# main.net
KiCad netlist of a schematic drawn in EAGLE
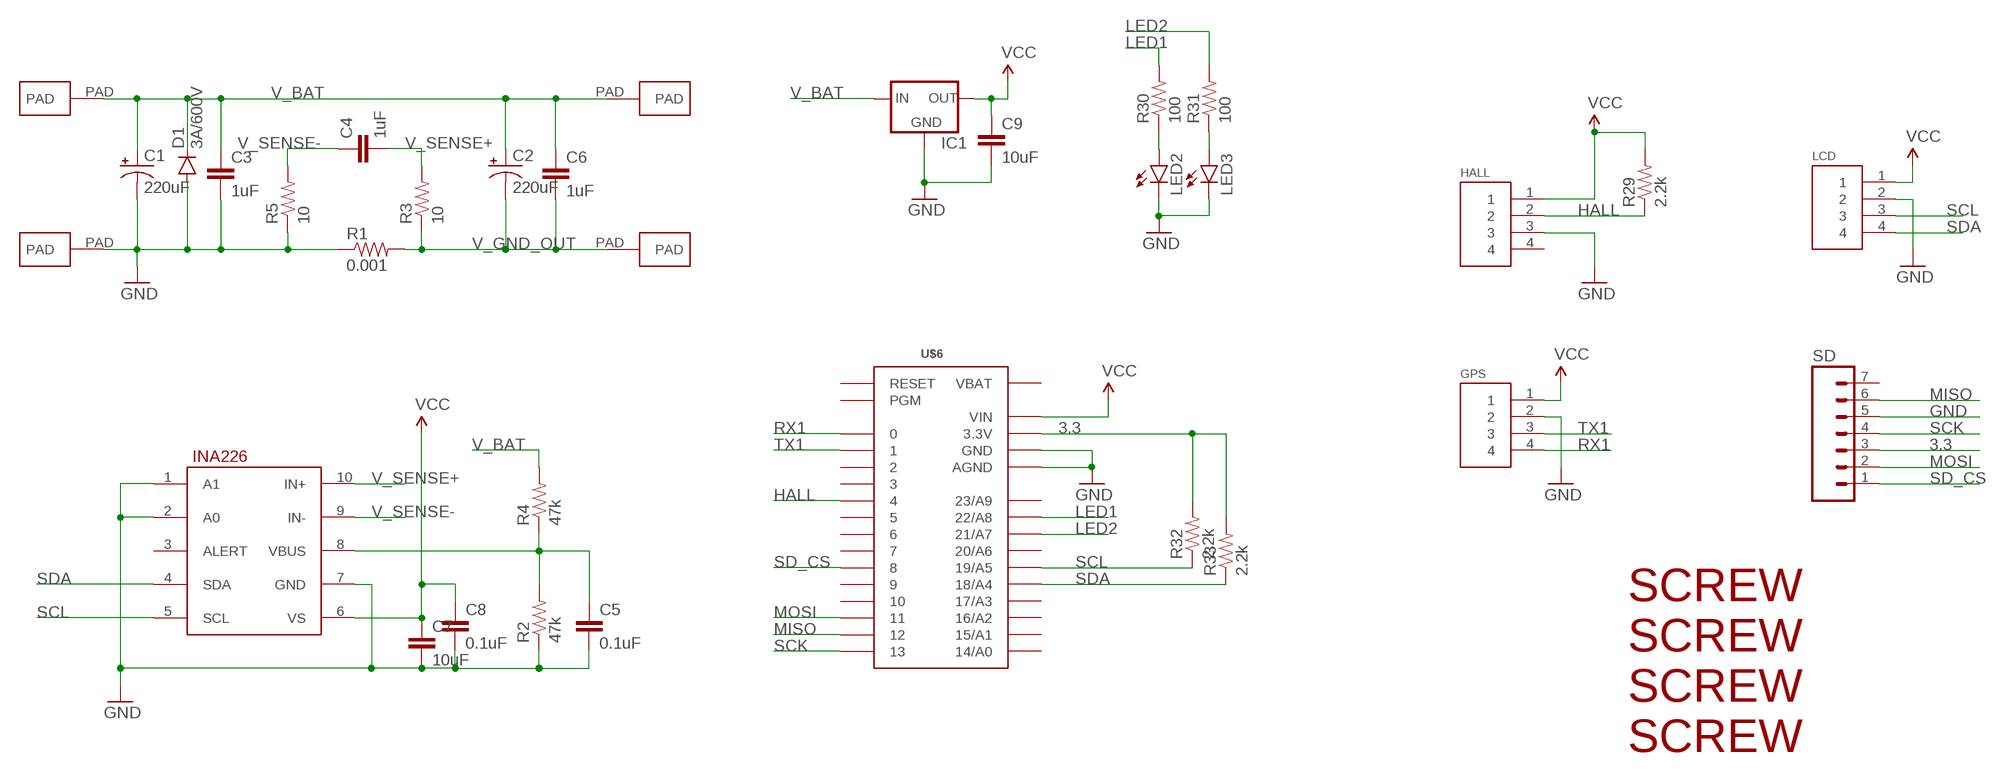
[diagram p0: schematic, sheet 1]

(export (version "E")
  (design (tool "Eeschema 10.0.6"))
  (components
    (comp (ref "C1")
      (value "220uF")
      (footprint "eagle-import:CPOL-RADIAL-1000UF-25V")
      (libsource (lib "eagle-import") (part "CAP_POLPTH4"))
    )
    (comp (ref "C2")
      (value "220uF")
      (footprint "eagle-import:CPOL-RADIAL-1000UF-25V")
      (libsource (lib "eagle-import") (part "CAP_POLPTH4"))
    )
    (comp (ref "C3")
      (value "1uF")
      (footprint "eagle-import:1206")
      (libsource (lib "eagle-import") (part "CAP1206"))
    )
    (comp (ref "C4")
      (value "1uF")
      (footprint "eagle-import:1206")
      (libsource (lib "eagle-import") (part "CAP1206"))
    )
    (comp (ref "C5")
      (value "0.1uF")
      (footprint "eagle-import:0603-CAP")
      (libsource (lib "eagle-import") (part "SparkFun-Passives_CAP0603-CAP"))
    )
    (comp (ref "C6")
      (value "1uF")
      (footprint "eagle-import:1206")
      (libsource (lib "eagle-import") (part "CAP1206"))
    )
    (comp (ref "C7")
      (value "10uF")
      (footprint "eagle-import:0805")
      (libsource (lib "eagle-import") (part "SparkFun-Passives_CAP0805"))
    )
    (comp (ref "C8")
      (value "0.1uF")
      (footprint "eagle-import:0603-CAP")
      (libsource (lib "eagle-import") (part "SparkFun-Passives_CAP0603-CAP"))
    )
    (comp (ref "C9")
      (value "10uF")
      (footprint "eagle-import:0805")
      (libsource (lib "eagle-import") (part "SparkFun-Passives_CAP0805"))
    )
    (comp (ref "D1")
      (value "3A/600V")
      (footprint "eagle-import:SMC")
      (libsource (lib "eagle-import") (part "DIODEES3J"))
    )
    (comp (ref "GPS")
      (value "GPS")
      (footprint "eagle-import:4PINVALULOK")
      (libsource (lib "eagle-import") (part "HEADER4VALULOK"))
    )
    (comp (ref "HALL")
      (value "HEADER4VALULOK")
      (footprint "eagle-import:4PINVALULOK")
      (libsource (lib "eagle-import") (part "HEADER4VALULOK"))
    )
    (comp (ref "IC1")
      (value "V_REG_78XXSINK")
      (footprint "eagle-import:TO220-IGO")
      (libsource (lib "eagle-import") (part "V_REG_78XXSINK"))
    )
    (comp (ref "LCD")
      (value "GPS")
      (footprint "eagle-import:4PINVALULOK")
      (libsource (lib "eagle-import") (part "HEADER4VALULOK"))
    )
    (comp (ref "LED2")
      (value "LED1206")
      (footprint "eagle-import:LED-1206")
      (libsource (lib "eagle-import") (part "LED1206"))
    )
    (comp (ref "LED3")
      (value "LED1206")
      (footprint "eagle-import:LED-1206")
      (libsource (lib "eagle-import") (part "LED1206"))
    )
    (comp (ref "R1")
      (value "0.001")
      (footprint "eagle-import:R2512")
      (libsource (lib "eagle-import") (part "SparkFun-Resistors_RESISTOR2512"))
    )
    (comp (ref "R2")
      (value "47k")
      (footprint "eagle-import:0603-RES")
      (libsource (lib "eagle-import") (part "RESISTOR0603-RES"))
    )
    (comp (ref "R3")
      (value "10")
      (footprint "eagle-import:0603-RES")
      (libsource (lib "eagle-import") (part "RESISTOR0603-RES"))
    )
    (comp (ref "R4")
      (value "47k")
      (footprint "eagle-import:0603-RES")
      (libsource (lib "eagle-import") (part "RESISTOR0603-RES"))
    )
    (comp (ref "R5")
      (value "10")
      (footprint "eagle-import:0603-RES")
      (libsource (lib "eagle-import") (part "RESISTOR0603-RES"))
    )
    (comp (ref "R29")
      (value "2.2k")
      (footprint "eagle-import:0603-RES")
      (libsource (lib "eagle-import") (part "RESISTOR0603-RES"))
    )
    (comp (ref "R30")
      (value "100")
      (footprint "eagle-import:0603-RES")
      (libsource (lib "eagle-import") (part "RESISTOR0603-RES"))
    )
    (comp (ref "R31")
      (value "100")
      (footprint "eagle-import:0603-RES")
      (libsource (lib "eagle-import") (part "RESISTOR0603-RES"))
    )
    (comp (ref "R32")
      (value "2.2k")
      (footprint "eagle-import:0603-RES")
      (libsource (lib "eagle-import") (part "RESISTOR0603-RES"))
    )
    (comp (ref "R33")
      (value "2.2k")
      (footprint "eagle-import:0603-RES")
      (libsource (lib "eagle-import") (part "RESISTOR0603-RES"))
    )
    (comp (ref "SD")
      (value "M07")
      (footprint "eagle-import:1X07")
      (libsource (lib "eagle-import") (part "M07"))
    )
    (comp (ref "U$1")
      (value "INA226")
      (footprint "eagle-import:PSOP-10")
      (libsource (lib "eagle-import") (part "INA226"))
    )
    (comp (ref "U$2")
      (value "PAD")
      (footprint "eagle-import:PAD")
      (libsource (lib "eagle-import") (part "PAD"))
    )
    (comp (ref "U$3")
      (value "PAD")
      (footprint "eagle-import:PAD")
      (libsource (lib "eagle-import") (part "PAD"))
    )
    (comp (ref "U$4")
      (value "PAD")
      (footprint "eagle-import:PAD")
      (libsource (lib "eagle-import") (part "PAD"))
    )
    (comp (ref "U$5")
      (value "PAD")
      (footprint "eagle-import:PAD")
      (libsource (lib "eagle-import") (part "PAD"))
    )
    (comp (ref "U$6")
      (value "TEENSY_3.0_BASIC")
      (footprint "eagle-import:TEENSY_3.0_BASIC")
      (libsource (lib "eagle-import") (part "TEENSY_3.0_BASIC"))
    )
    (comp (ref "U$13")
      (value "SCREW")
      (footprint "eagle-import:M3HOLE")
      (libsource (lib "eagle-import") (part "SCREW"))
    )
    (comp (ref "U$14")
      (value "SCREW")
      (footprint "eagle-import:M3HOLE")
      (libsource (lib "eagle-import") (part "SCREW"))
    )
    (comp (ref "U$15")
      (value "SCREW")
      (footprint "eagle-import:M3HOLE")
      (libsource (lib "eagle-import") (part "SCREW"))
    )
    (comp (ref "U$16")
      (value "SCREW")
      (footprint "eagle-import:M3HOLE")
      (libsource (lib "eagle-import") (part "SCREW"))
    )
  )
  (nets
    (net (code "1") (name "/3.3") (class "Default")
      (node (ref "R32") (pin "2") (pinfunction "2_2") (pintype "passive"))
      (node (ref "R33") (pin "2") (pinfunction "2_2") (pintype "passive"))
      (node (ref "SD") (pin "3") (pinfunction "3_3") (pintype "passive"))
      (node (ref "U$6") (pin "3.3V") (pinfunction "3.3V_3.3V") (pintype "power_in"))
      (node (ref "U$6") (pin "3.3V1") (pinfunction "3.3V_3.3V1") (pintype "power_in"))
    )
    (net (code "2") (name "/HALL") (class "Default")
      (node (ref "HALL") (pin "2") (pinfunction "2_2") (pintype "bidirectional"))
      (node (ref "R29") (pin "1") (pinfunction "1_1") (pintype "passive"))
      (node (ref "U$6") (pin "4") (pinfunction "4_4") (pintype "bidirectional"))
    )
    (net (code "3") (name "/LED1") (class "Default")
      (node (ref "R30") (pin "2") (pinfunction "2_2") (pintype "passive"))
      (node (ref "U$6") (pin "22/A8") (pinfunction "22/A8_22/A8") (pintype "bidirectional"))
    )
    (net (code "4") (name "/LED2") (class "Default")
      (node (ref "R31") (pin "2") (pinfunction "2_2") (pintype "passive"))
      (node (ref "U$6") (pin "21/A7") (pinfunction "21/A7_21/A7") (pintype "bidirectional"))
    )
    (net (code "5") (name "/MISO") (class "Default")
      (node (ref "SD") (pin "6") (pinfunction "6_6") (pintype "passive"))
      (node (ref "U$6") (pin "12") (pinfunction "12_12") (pintype "bidirectional"))
    )
    (net (code "6") (name "/MOSI") (class "Default")
      (node (ref "SD") (pin "2") (pinfunction "2_2") (pintype "passive"))
      (node (ref "U$6") (pin "11") (pinfunction "11_11") (pintype "bidirectional"))
    )
    (net (code "7") (name "/RX1") (class "Default")
      (node (ref "GPS") (pin "4") (pinfunction "4_4") (pintype "bidirectional"))
      (node (ref "U$6") (pin "0") (pinfunction "0_0") (pintype "bidirectional"))
    )
    (net (code "8") (name "/SCK") (class "Default")
      (node (ref "SD") (pin "4") (pinfunction "4_4") (pintype "passive"))
      (node (ref "U$6") (pin "13") (pinfunction "13_13") (pintype "bidirectional"))
    )
    (net (code "9") (name "/SCL") (class "Default")
      (node (ref "LCD") (pin "3") (pinfunction "3_3") (pintype "bidirectional"))
      (node (ref "R32") (pin "1") (pinfunction "1_1") (pintype "passive"))
      (node (ref "U$1") (pin "5") (pinfunction "SCL_5") (pintype "bidirectional"))
      (node (ref "U$6") (pin "19/A5") (pinfunction "19/A5_19/A5") (pintype "bidirectional"))
    )
    (net (code "10") (name "/SDA") (class "Default")
      (node (ref "LCD") (pin "4") (pinfunction "4_4") (pintype "bidirectional"))
      (node (ref "R33") (pin "1") (pinfunction "1_1") (pintype "passive"))
      (node (ref "U$1") (pin "4") (pinfunction "SDA_4") (pintype "bidirectional"))
      (node (ref "U$6") (pin "18/A4") (pinfunction "18/A4_18/A4") (pintype "bidirectional"))
    )
    (net (code "11") (name "/SD_CS") (class "Default")
      (node (ref "SD") (pin "1") (pinfunction "1_1") (pintype "passive"))
      (node (ref "U$6") (pin "8") (pinfunction "8_8") (pintype "bidirectional"))
    )
    (net (code "12") (name "/TX1") (class "Default")
      (node (ref "GPS") (pin "3") (pinfunction "3_3") (pintype "bidirectional"))
      (node (ref "U$6") (pin "1") (pinfunction "1_1") (pintype "bidirectional"))
    )
    (net (code "13") (name "/VBAT") (class "Default")
      (node (ref "U$6") (pin "VBAT") (pinfunction "VBAT_VBAT") (pintype "power_in"))
    )
    (net (code "14") (name "/V_BAT") (class "Default")
      (node (ref "C1") (pin "+") (pinfunction "+_+") (pintype "passive"))
      (node (ref "C2") (pin "+") (pinfunction "+_+") (pintype "passive"))
      (node (ref "C3") (pin "1") (pinfunction "1_1") (pintype "passive"))
      (node (ref "C6") (pin "1") (pinfunction "1_1") (pintype "passive"))
      (node (ref "D1") (pin "C") (pinfunction "C_C") (pintype "passive"))
      (node (ref "IC1") (pin "IN") (pinfunction "IN_IN") (pintype "input"))
      (node (ref "R4") (pin "2") (pinfunction "2_2") (pintype "passive"))
      (node (ref "U$2") (pin "PAD") (pinfunction "PAD_PAD") (pintype "bidirectional"))
      (node (ref "U$4") (pin "PAD") (pinfunction "PAD_PAD") (pintype "bidirectional"))
    )
    (net (code "15") (name "/V_GND_OUT") (class "Default")
      (node (ref "C2") (pin "-") (pinfunction "-_-") (pintype "passive"))
      (node (ref "C6") (pin "2") (pinfunction "2_2") (pintype "passive"))
      (node (ref "R1") (pin "2") (pinfunction "2_2") (pintype "passive"))
      (node (ref "R3") (pin "1") (pinfunction "1_1") (pintype "passive"))
      (node (ref "U$5") (pin "PAD") (pinfunction "PAD_PAD") (pintype "bidirectional"))
    )
    (net (code "16") (name "/V_SENSE+") (class "Default")
      (node (ref "C4") (pin "2") (pinfunction "2_2") (pintype "passive"))
      (node (ref "R3") (pin "2") (pinfunction "2_2") (pintype "passive"))
      (node (ref "U$1") (pin "10") (pinfunction "IN+_10") (pintype "bidirectional"))
    )
    (net (code "17") (name "/V_SENSE-") (class "Default")
      (node (ref "C4") (pin "1") (pinfunction "1_1") (pintype "passive"))
      (node (ref "R5") (pin "2") (pinfunction "2_2") (pintype "passive"))
      (node (ref "U$1") (pin "9") (pinfunction "IN-_9") (pintype "bidirectional"))
    )
    (net (code "18") (name "GND") (class "Default")
      (node (ref "C1") (pin "-") (pinfunction "-_-") (pintype "passive"))
      (node (ref "C3") (pin "2") (pinfunction "2_2") (pintype "passive"))
      (node (ref "C5") (pin "2") (pinfunction "2_2") (pintype "passive"))
      (node (ref "C7") (pin "2") (pinfunction "2_2") (pintype "passive"))
      (node (ref "C8") (pin "2") (pinfunction "2_2") (pintype "passive"))
      (node (ref "C9") (pin "2") (pinfunction "2_2") (pintype "passive"))
      (node (ref "D1") (pin "A") (pinfunction "A_A") (pintype "passive"))
      (node (ref "GPS") (pin "2") (pinfunction "2_2") (pintype "bidirectional"))
      (node (ref "HALL") (pin "3") (pinfunction "3_3") (pintype "bidirectional"))
      (node (ref "IC1") (pin "GND") (pinfunction "GND_GND") (pintype "input"))
      (node (ref "LCD") (pin "2") (pinfunction "2_2") (pintype "bidirectional"))
      (node (ref "LED2") (pin "C") (pinfunction "C_C") (pintype "passive"))
      (node (ref "LED3") (pin "C") (pinfunction "C_C") (pintype "passive"))
      (node (ref "R1") (pin "1") (pinfunction "1_1") (pintype "passive"))
      (node (ref "R2") (pin "1") (pinfunction "1_1") (pintype "passive"))
      (node (ref "R5") (pin "1") (pinfunction "1_1") (pintype "passive"))
      (node (ref "SD") (pin "5") (pinfunction "5_5") (pintype "passive"))
      (node (ref "U$1") (pin "1") (pinfunction "A1_1") (pintype "bidirectional"))
      (node (ref "U$1") (pin "2") (pinfunction "A0_2") (pintype "bidirectional"))
      (node (ref "U$1") (pin "7") (pinfunction "GND_7") (pintype "bidirectional"))
      (node (ref "U$3") (pin "PAD") (pinfunction "PAD_PAD") (pintype "bidirectional"))
      (node (ref "U$6") (pin "AGND") (pinfunction "AGND_AGND") (pintype "power_in"))
      (node (ref "U$6") (pin "GND") (pinfunction "GND_GND") (pintype "power_in"))
      (node (ref "U$6") (pin "GND1") (pinfunction "GND_GND1") (pintype "power_in"))
    )
    (net (code "19") (name "Net-(LED2-PadA)") (class "Default")
      (node (ref "LED2") (pin "A") (pinfunction "A_A") (pintype "passive"))
      (node (ref "R30") (pin "1") (pinfunction "1_1") (pintype "passive"))
    )
    (net (code "20") (name "Net-(LED3-PadA)") (class "Default")
      (node (ref "LED3") (pin "A") (pinfunction "A_A") (pintype "passive"))
      (node (ref "R31") (pin "1") (pinfunction "1_1") (pintype "passive"))
    )
    (net (code "21") (name "Net-(U$1-VBUS)") (class "Default")
      (node (ref "C5") (pin "1") (pinfunction "1_1") (pintype "passive"))
      (node (ref "R2") (pin "2") (pinfunction "2_2") (pintype "passive"))
      (node (ref "R4") (pin "1") (pinfunction "1_1") (pintype "passive"))
      (node (ref "U$1") (pin "8") (pinfunction "VBUS_8") (pintype "bidirectional"))
    )
    (net (code "22") (name "VCC") (class "Default")
      (node (ref "C7") (pin "1") (pinfunction "1_1") (pintype "passive"))
      (node (ref "C8") (pin "1") (pinfunction "1_1") (pintype "passive"))
      (node (ref "C9") (pin "1") (pinfunction "1_1") (pintype "passive"))
      (node (ref "GPS") (pin "1") (pinfunction "1_1") (pintype "bidirectional"))
      (node (ref "HALL") (pin "1") (pinfunction "1_1") (pintype "bidirectional"))
      (node (ref "IC1") (pin "OUT") (pinfunction "OUT_OUT") (pintype "output"))
      (node (ref "LCD") (pin "1") (pinfunction "1_1") (pintype "bidirectional"))
      (node (ref "R29") (pin "2") (pinfunction "2_2") (pintype "passive"))
      (node (ref "U$1") (pin "6") (pinfunction "VS_6") (pintype "bidirectional"))
      (node (ref "U$6") (pin "VIN") (pinfunction "VIN_VIN") (pintype "power_in"))
    )
    (net (code "23") (name "unconnected-(HALL-Pad4)") (class "Default")
      (node (ref "HALL") (pin "4") (pinfunction "4_4") (pintype "bidirectional"))
    )
    (net (code "24") (name "unconnected-(SD-Pad7)") (class "Default")
      (node (ref "SD") (pin "7") (pinfunction "7_7") (pintype "passive"))
    )
    (net (code "25") (name "unconnected-(U$1-ALERT-Pad3)") (class "Default")
      (node (ref "U$1") (pin "3") (pinfunction "ALERT_3") (pintype "bidirectional"))
    )
    (net (code "26") (name "unconnected-(U$6-Pad2)") (class "Default")
      (node (ref "U$6") (pin "2") (pinfunction "2_2") (pintype "bidirectional"))
    )
    (net (code "27") (name "unconnected-(U$6-Pad3)") (class "Default")
      (node (ref "U$6") (pin "3") (pinfunction "3_3") (pintype "bidirectional"))
    )
    (net (code "28") (name "unconnected-(U$6-Pad5)") (class "Default")
      (node (ref "U$6") (pin "5") (pinfunction "5_5") (pintype "bidirectional"))
    )
    (net (code "29") (name "unconnected-(U$6-Pad6)") (class "Default")
      (node (ref "U$6") (pin "6") (pinfunction "6_6") (pintype "bidirectional"))
    )
    (net (code "30") (name "unconnected-(U$6-Pad7)") (class "Default")
      (node (ref "U$6") (pin "7") (pinfunction "7_7") (pintype "bidirectional"))
    )
    (net (code "31") (name "unconnected-(U$6-Pad9)") (class "Default")
      (node (ref "U$6") (pin "9") (pinfunction "9_9") (pintype "bidirectional"))
    )
    (net (code "32") (name "unconnected-(U$6-Pad10)") (class "Default")
      (node (ref "U$6") (pin "10") (pinfunction "10_10") (pintype "bidirectional"))
    )
    (net (code "33") (name "unconnected-(U$6-Pad14{slash}A0)") (class "Default")
      (node (ref "U$6") (pin "14/A0") (pinfunction "14/A0_14/A0") (pintype "bidirectional"))
    )
    (net (code "34") (name "unconnected-(U$6-Pad15{slash}A1)") (class "Default")
      (node (ref "U$6") (pin "15/A1") (pinfunction "15/A1_15/A1") (pintype "bidirectional"))
    )
    (net (code "35") (name "unconnected-(U$6-Pad16{slash}A2)") (class "Default")
      (node (ref "U$6") (pin "16/A2") (pinfunction "16/A2_16/A2") (pintype "bidirectional"))
    )
    (net (code "36") (name "unconnected-(U$6-Pad17{slash}A3)") (class "Default")
      (node (ref "U$6") (pin "17/A3") (pinfunction "17/A3_17/A3") (pintype "bidirectional"))
    )
    (net (code "37") (name "unconnected-(U$6-Pad20{slash}A6)") (class "Default")
      (node (ref "U$6") (pin "20/A6") (pinfunction "20/A6_20/A6") (pintype "bidirectional"))
    )
    (net (code "38") (name "unconnected-(U$6-Pad23{slash}A9)") (class "Default")
      (node (ref "U$6") (pin "23/A9") (pinfunction "23/A9_23/A9") (pintype "bidirectional"))
    )
    (net (code "39") (name "unconnected-(U$6-PadPGM)") (class "Default")
      (node (ref "U$6") (pin "PGM") (pinfunction "PGM_PGM") (pintype "bidirectional"))
    )
    (net (code "40") (name "unconnected-(U$6-PadRESET)") (class "Default")
      (node (ref "U$6") (pin "RESET") (pinfunction "RESET_RESET") (pintype "bidirectional"))
    )
  )
)
